# main.net
KiCad netlist of a schematic drawn in EAGLE
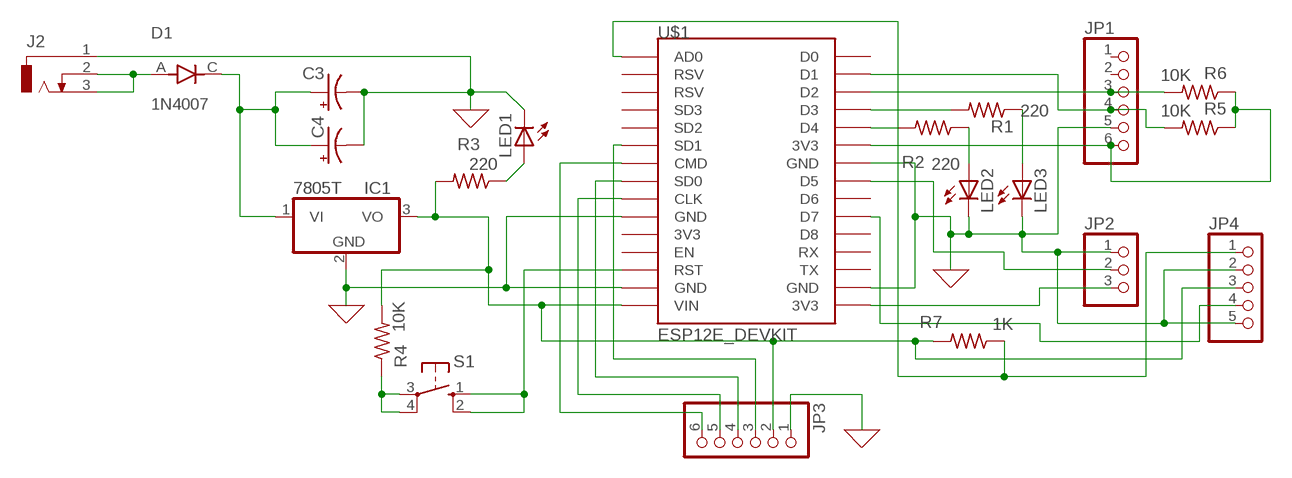
[diagram p0: schematic, sheet 1]

(export (version "E")
  (design (tool "Eeschema 10.0.6"))
  (components
    (comp (ref "C3")
      (value "CPOL-USE2,5-6E")
      (footprint "eagle-import:E2,5-6E")
      (libsource (lib "eagle-import") (part "CPOL-USE2,5-6E"))
    )
    (comp (ref "C4")
      (value "CPOL-USE2,5-6E")
      (footprint "eagle-import:E2,5-6E")
      (libsource (lib "eagle-import") (part "CPOL-USE2,5-6E"))
    )
    (comp (ref "D1")
      (value "1N4007")
      (footprint "eagle-import:DIOAD1060W80L520D270")
      (fields (field (name "MF") "ON Semiconductor"))
      (libsource (lib "eagle-import") (part "1N4007"))
    )
    (comp (ref "IC1")
      (value "7805T")
      (footprint "eagle-import:TO220H")
      (libsource (lib "eagle-import") (part "78T05"))
    )
    (comp (ref "J2")
      (value "DCJ0303")
      (footprint "eagle-import:DCJ0303")
      (libsource (lib "eagle-import") (part "DCJ0303"))
    )
    (comp (ref "JP1")
      (value "PINHD-1X6")
      (footprint "eagle-import:1X06")
      (libsource (lib "eagle-import") (part "PINHD-1X6"))
    )
    (comp (ref "JP2")
      (value "PINHD-1X3")
      (footprint "eagle-import:1X03")
      (libsource (lib "eagle-import") (part "PINHD-1X3"))
    )
    (comp (ref "JP3")
      (value "PINHD-1X6")
      (footprint "eagle-import:1X06")
      (libsource (lib "eagle-import") (part "PINHD-1X6"))
    )
    (comp (ref "JP4")
      (value "PINHD-1X55X2MM")
      (footprint "eagle-import:1_05X2MM")
      (libsource (lib "eagle-import") (part "PINHD-1X55X2MM"))
    )
    (comp (ref "LED1")
      (value "LED3MM")
      (footprint "eagle-import:LED3MM")
      (libsource (lib "eagle-import") (part "LED3MM"))
    )
    (comp (ref "LED2")
      (value "LED3MM")
      (footprint "eagle-import:LED3MM")
      (libsource (lib "eagle-import") (part "LED3MM"))
    )
    (comp (ref "LED3")
      (value "LED3MM")
      (footprint "eagle-import:LED3MM")
      (libsource (lib "eagle-import") (part "LED3MM"))
    )
    (comp (ref "R1")
      (value "220")
      (footprint "eagle-import:0805-THM")
      (libsource (lib "eagle-import") (part "FLIPFLOP-RES"))
    )
    (comp (ref "R2")
      (value "220")
      (footprint "eagle-import:0805-THM")
      (libsource (lib "eagle-import") (part "FLIPFLOP-RES"))
    )
    (comp (ref "R3")
      (value "220")
      (footprint "eagle-import:0805-THM")
      (libsource (lib "eagle-import") (part "FLIPFLOP-RES"))
    )
    (comp (ref "R4")
      (value "10K")
      (footprint "eagle-import:0805-THM")
      (libsource (lib "eagle-import") (part "FLIPFLOP-RES"))
    )
    (comp (ref "R5")
      (value "10K")
      (footprint "eagle-import:0805-THM")
      (libsource (lib "eagle-import") (part "FLIPFLOP-RES"))
    )
    (comp (ref "R6")
      (value "10K")
      (footprint "eagle-import:0805-THM")
      (libsource (lib "eagle-import") (part "FLIPFLOP-RES"))
    )
    (comp (ref "R7")
      (value "1K")
      (footprint "eagle-import:0805-THM")
      (libsource (lib "eagle-import") (part "FLIPFLOP-RES"))
    )
    (comp (ref "S1")
      (value "10-XX")
      (footprint "eagle-import:B3F-10XX")
      (fields (field (name "MPN") "B3F-1000"))
      (libsource (lib "eagle-import") (part "10-XX"))
    )
    (comp (ref "U$1")
      (value "ESP12E_DEVKIT")
      (footprint "eagle-import:ESP12E_DEVKIT")
      (libsource (lib "eagle-import") (part "ESP12E_DEVKIT"))
    )
  )
  (nets
    (net (code "1") (name "GND") (class "Default")
      (node (ref "C3") (pin "-") (pinfunction "-_-") (pintype "passive"))
      (node (ref "C4") (pin "-") (pinfunction "-_-") (pintype "passive"))
      (node (ref "IC1") (pin "2") (pinfunction "GND_2") (pintype "passive"))
      (node (ref "J2") (pin "1") (pinfunction "1_1") (pintype "passive"))
      (node (ref "JP1") (pin "5") (pinfunction "5_5") (pintype "passive"))
      (node (ref "JP2") (pin "1") (pinfunction "1_1") (pintype "passive"))
      (node (ref "JP3") (pin "1") (pinfunction "1_1") (pintype "passive"))
      (node (ref "JP4") (pin "2") (pinfunction "2_2") (pintype "passive"))
      (node (ref "JP4") (pin "5") (pinfunction "5_5") (pintype "passive"))
      (node (ref "LED1") (pin "K") (pinfunction "C_K") (pintype "passive"))
      (node (ref "LED2") (pin "K") (pinfunction "C_K") (pintype "passive"))
      (node (ref "LED3") (pin "K") (pinfunction "C_K") (pintype "passive"))
      (node (ref "U$1") (pin "GND@0") (pinfunction "GND_GND@0") (pintype "bidirectional"))
      (node (ref "U$1") (pin "GND@1") (pinfunction "GND_GND@1") (pintype "bidirectional"))
      (node (ref "U$1") (pin "GND@2") (pinfunction "GND_GND@2") (pintype "bidirectional"))
      (node (ref "U$1") (pin "GND@3") (pinfunction "GND_GND@3") (pintype "bidirectional"))
    )
    (net (code "2") (name "Net-(D1-PadA)") (class "Default")
      (node (ref "D1") (pin "A") (pinfunction "A_A") (pintype "passive"))
      (node (ref "J2") (pin "2") (pinfunction "2_2") (pintype "passive"))
      (node (ref "J2") (pin "3") (pinfunction "3_3") (pintype "passive"))
    )
    (net (code "3") (name "Net-(IC1-VI)") (class "Default")
      (node (ref "C3") (pin "+") (pinfunction "+_+") (pintype "passive"))
      (node (ref "C4") (pin "+") (pinfunction "+_+") (pintype "passive"))
      (node (ref "D1") (pin "C") (pinfunction "C_C") (pintype "passive"))
      (node (ref "IC1") (pin "1") (pinfunction "VI_1") (pintype "input"))
    )
    (net (code "4") (name "Net-(IC1-VO)") (class "Default")
      (node (ref "IC1") (pin "3") (pinfunction "VO_3") (pintype "passive"))
      (node (ref "JP3") (pin "2") (pinfunction "2_2") (pintype "passive"))
      (node (ref "JP4") (pin "3") (pinfunction "3_3") (pintype "passive"))
      (node (ref "R3") (pin "2") (pinfunction "2_2") (pintype "passive"))
      (node (ref "R4") (pin "2") (pinfunction "2_2") (pintype "passive"))
      (node (ref "R7") (pin "2") (pinfunction "2_2") (pintype "passive"))
      (node (ref "U$1") (pin "VIN") (pinfunction "VIN_VIN") (pintype "bidirectional"))
    )
    (net (code "5") (name "Net-(JP1-Pad3)") (class "Default")
      (node (ref "JP1") (pin "3") (pinfunction "3_3") (pintype "passive"))
      (node (ref "R6") (pin "2") (pinfunction "2_2") (pintype "passive"))
      (node (ref "U$1") (pin "D2") (pinfunction "D2_D2") (pintype "bidirectional"))
    )
    (net (code "6") (name "Net-(JP1-Pad4)") (class "Default")
      (node (ref "JP1") (pin "4") (pinfunction "4_4") (pintype "passive"))
      (node (ref "R5") (pin "2") (pinfunction "2_2") (pintype "passive"))
      (node (ref "U$1") (pin "D1") (pinfunction "D1_D1") (pintype "bidirectional"))
    )
    (net (code "7") (name "Net-(JP1-Pad6)") (class "Default")
      (node (ref "JP1") (pin "6") (pinfunction "6_6") (pintype "passive"))
      (node (ref "R5") (pin "1") (pinfunction "1_1") (pintype "passive"))
      (node (ref "R6") (pin "1") (pinfunction "1_1") (pintype "passive"))
      (node (ref "U$1") (pin "3V3@1") (pinfunction "3V3_3V3@1") (pintype "bidirectional"))
    )
    (net (code "8") (name "Net-(JP2-Pad2)") (class "Default")
      (node (ref "JP2") (pin "2") (pinfunction "2_2") (pintype "passive"))
      (node (ref "U$1") (pin "D5") (pinfunction "D5_D5") (pintype "bidirectional"))
    )
    (net (code "9") (name "Net-(JP2-Pad3)") (class "Default")
      (node (ref "JP2") (pin "3") (pinfunction "3_3") (pintype "passive"))
      (node (ref "U$1") (pin "3V3@2") (pinfunction "3V3_3V3@2") (pintype "bidirectional"))
    )
    (net (code "10") (name "Net-(JP3-Pad3)") (class "Default")
      (node (ref "JP3") (pin "3") (pinfunction "3_3") (pintype "passive"))
      (node (ref "U$1") (pin "SD1") (pinfunction "SD1_SD1") (pintype "bidirectional"))
    )
    (net (code "11") (name "Net-(JP3-Pad4)") (class "Default")
      (node (ref "JP3") (pin "4") (pinfunction "4_4") (pintype "passive"))
      (node (ref "U$1") (pin "SD0") (pinfunction "SD0_SD0") (pintype "bidirectional"))
    )
    (net (code "12") (name "Net-(JP3-Pad5)") (class "Default")
      (node (ref "JP3") (pin "5") (pinfunction "5_5") (pintype "passive"))
      (node (ref "U$1") (pin "CLK") (pinfunction "CLK_CLK") (pintype "bidirectional"))
    )
    (net (code "13") (name "Net-(JP3-Pad6)") (class "Default")
      (node (ref "JP3") (pin "6") (pinfunction "6_6") (pintype "passive"))
      (node (ref "U$1") (pin "CMD") (pinfunction "CMD_CMD") (pintype "bidirectional"))
    )
    (net (code "14") (name "Net-(JP4-Pad1)") (class "Default")
      (node (ref "JP4") (pin "1") (pinfunction "1_1") (pintype "passive"))
      (node (ref "R7") (pin "1") (pinfunction "1_1") (pintype "passive"))
      (node (ref "U$1") (pin "AD0") (pinfunction "AD0_AD0") (pintype "bidirectional"))
    )
    (net (code "15") (name "Net-(JP4-Pad4)") (class "Default")
      (node (ref "JP4") (pin "4") (pinfunction "4_4") (pintype "passive"))
      (node (ref "U$1") (pin "D7") (pinfunction "D7_D7") (pintype "bidirectional"))
    )
    (net (code "16") (name "Net-(LED1-PadA)") (class "Default")
      (node (ref "LED1") (pin "A") (pinfunction "A_A") (pintype "passive"))
      (node (ref "R3") (pin "1") (pinfunction "1_1") (pintype "passive"))
    )
    (net (code "17") (name "Net-(LED2-PadA)") (class "Default")
      (node (ref "LED2") (pin "A") (pinfunction "A_A") (pintype "passive"))
      (node (ref "R2") (pin "1") (pinfunction "1_1") (pintype "passive"))
    )
    (net (code "18") (name "Net-(LED3-PadA)") (class "Default")
      (node (ref "LED3") (pin "A") (pinfunction "A_A") (pintype "passive"))
      (node (ref "R1") (pin "1") (pinfunction "1_1") (pintype "passive"))
    )
    (net (code "19") (name "Net-(R1-Pad2)") (class "Default")
      (node (ref "R1") (pin "2") (pinfunction "2_2") (pintype "passive"))
      (node (ref "U$1") (pin "D3") (pinfunction "D3_D3") (pintype "bidirectional"))
    )
    (net (code "20") (name "Net-(R2-Pad2)") (class "Default")
      (node (ref "R2") (pin "2") (pinfunction "2_2") (pintype "passive"))
      (node (ref "U$1") (pin "D4") (pinfunction "D4_D4") (pintype "bidirectional"))
    )
    (net (code "21") (name "Net-(S1-P)") (class "Default")
      (node (ref "R4") (pin "1") (pinfunction "1_1") (pintype "passive"))
      (node (ref "S1") (pin "3") (pinfunction "P_3") (pintype "passive"))
      (node (ref "S1") (pin "4") (pinfunction "P1_4") (pintype "passive"))
    )
    (net (code "22") (name "Net-(S1-S)") (class "Default")
      (node (ref "S1") (pin "1") (pinfunction "S_1") (pintype "passive"))
      (node (ref "S1") (pin "2") (pinfunction "S1_2") (pintype "passive"))
      (node (ref "U$1") (pin "RST") (pinfunction "RST_RST") (pintype "bidirectional"))
    )
    (net (code "23") (name "unconnected-(JP1-Pad1)") (class "Default")
      (node (ref "JP1") (pin "1") (pinfunction "1_1") (pintype "passive"))
    )
    (net (code "24") (name "unconnected-(JP1-Pad2)") (class "Default")
      (node (ref "JP1") (pin "2") (pinfunction "2_2") (pintype "passive"))
    )
    (net (code "25") (name "unconnected-(U$1-3V3-Pad3V3@0)") (class "Default")
      (node (ref "U$1") (pin "3V3@0") (pinfunction "3V3_3V3@0") (pintype "bidirectional"))
    )
    (net (code "26") (name "unconnected-(U$1-PadD0)") (class "Default")
      (node (ref "U$1") (pin "D0") (pinfunction "D0_D0") (pintype "bidirectional"))
    )
    (net (code "27") (name "unconnected-(U$1-PadD6)") (class "Default")
      (node (ref "U$1") (pin "D6") (pinfunction "D6_D6") (pintype "bidirectional"))
    )
    (net (code "28") (name "unconnected-(U$1-PadD8)") (class "Default")
      (node (ref "U$1") (pin "D8") (pinfunction "D8_D8") (pintype "bidirectional"))
    )
    (net (code "29") (name "unconnected-(U$1-PadEN)") (class "Default")
      (node (ref "U$1") (pin "EN") (pinfunction "EN_EN") (pintype "bidirectional"))
    )
    (net (code "30") (name "unconnected-(U$1-PadRX)") (class "Default")
      (node (ref "U$1") (pin "RX") (pinfunction "RX_RX") (pintype "bidirectional"))
    )
    (net (code "31") (name "unconnected-(U$1-PadSD2)") (class "Default")
      (node (ref "U$1") (pin "SD2") (pinfunction "SD2_SD2") (pintype "bidirectional"))
    )
    (net (code "32") (name "unconnected-(U$1-PadSD3)") (class "Default")
      (node (ref "U$1") (pin "SD3") (pinfunction "SD3_SD3") (pintype "bidirectional"))
    )
    (net (code "33") (name "unconnected-(U$1-PadTX)") (class "Default")
      (node (ref "U$1") (pin "TX") (pinfunction "TX_TX") (pintype "bidirectional"))
    )
    (net (code "34") (name "unconnected-(U$1-RSV-PadRSV@0)") (class "Default")
      (node (ref "U$1") (pin "RSV@0") (pinfunction "RSV_RSV@0") (pintype "bidirectional"))
    )
    (net (code "35") (name "unconnected-(U$1-RSV-PadRSV@1)") (class "Default")
      (node (ref "U$1") (pin "RSV@1") (pinfunction "RSV_RSV@1") (pintype "bidirectional"))
    )
  )
)
